# Laser_Driver.net
KiCad netlist of a schematic drawn in EAGLE
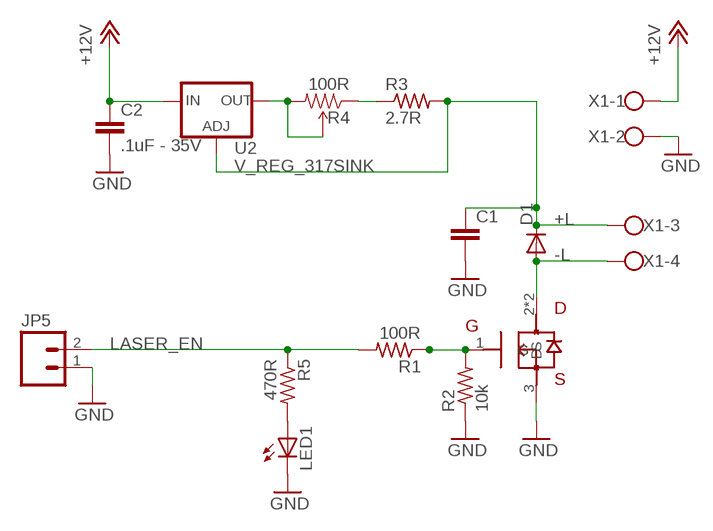
[diagram p0: schematic, sheet 1]

(export (version "E")
  (design (tool "Eeschema 10.0.6"))
  (components
    (comp (ref "C1")
      (value "C-EUC0805")
      (footprint "eagle-import:C0805")
      (libsource (lib "eagle-import") (part "C-EUC0805"))
    )
    (comp (ref "C2")
      (value ".1uF - 35V")
      (footprint "eagle-import:C1206")
      (libsource (lib "eagle-import") (part "C-EUC1206"))
    )
    (comp (ref "D1")
      (value "DIODEPTH")
      (footprint "eagle-import:DIODE-1N4001")
      (libsource (lib "eagle-import") (part "DIODEPTH"))
    )
    (comp (ref "JP5")
      (value "M02PTH")
      (footprint "eagle-import:1X02")
      (libsource (lib "eagle-import") (part "M02PTH"))
    )
    (comp (ref "LED1")
      (value "LEDCHIPLED_0805")
      (footprint "eagle-import:CHIPLED_0805")
      (libsource (lib "eagle-import") (part "LEDCHIPLED_0805"))
    )
    (comp (ref "R1")
      (value "100R")
      (footprint "eagle-import:R0805")
      (libsource (lib "eagle-import") (part "R-US_R0805"))
    )
    (comp (ref "R2")
      (value "10k")
      (footprint "eagle-import:R0805")
      (libsource (lib "eagle-import") (part "R-US_R0805"))
    )
    (comp (ref "R3")
      (value "2.7R")
      (footprint "eagle-import:0411_12")
      (libsource (lib "eagle-import") (part "R-US_0411/12"))
    )
    (comp (ref "R4")
      (value "100R")
      (footprint "eagle-import:3362U-2")
      (libsource (lib "eagle-import") (part "TRIMPOT"))
    )
    (comp (ref "R5")
      (value "470R")
      (footprint "eagle-import:R0805")
      (libsource (lib "eagle-import") (part "R-US_R0805"))
    )
    (comp (ref "U$2")
      (value "MOSFET")
      (footprint "eagle-import:SOT223")
      (libsource (lib "eagle-import") (part "MOSFET"))
    )
    (comp (ref "U2")
      (value "V_REG_317SINK")
      (footprint "eagle-import:TO220-ADJ")
      (libsource (lib "eagle-import") (part "V_REG_317SINK"))
    )
    (comp (ref "X1")
      (value "W237-4")
      (footprint "eagle-import:W237-4")
      (libsource (lib "eagle-import") (part "W237-4"))
    )
  )
  (nets
    (net (code "1") (name "+12V") (class "Default")
      (node (ref "C2") (pin "1") (pinfunction "1_1") (pintype "passive"))
      (node (ref "U2") (pin "IN") (pinfunction "IN_IN") (pintype "input"))
      (node (ref "X1") (pin "1") (pinfunction "KL_1") (pintype "passive"))
    )
    (net (code "2") (name "/+L") (class "Default")
      (node (ref "C1") (pin "1") (pinfunction "1_1") (pintype "passive"))
      (node (ref "D1") (pin "C") (pinfunction "C_C") (pintype "passive"))
      (node (ref "R3") (pin "2") (pinfunction "2_2") (pintype "passive"))
      (node (ref "U2") (pin "ADJ") (pinfunction "ADJ_ADJ") (pintype "input"))
      (node (ref "X1") (pin "3") (pinfunction "KL_3") (pintype "passive"))
    )
    (net (code "3") (name "/-L") (class "Default")
      (node (ref "D1") (pin "A") (pinfunction "A_A") (pintype "passive"))
      (node (ref "U$2") (pin "2") (pinfunction "D_2") (pintype "bidirectional"))
      (node (ref "U$2") (pin "4") (pinfunction "D_4") (pintype "bidirectional"))
      (node (ref "X1") (pin "4") (pinfunction "KL_4") (pintype "passive"))
    )
    (net (code "4") (name "/LASER_EN") (class "Default")
      (node (ref "JP5") (pin "2") (pinfunction "2_2") (pintype "passive"))
      (node (ref "R1") (pin "2") (pinfunction "2_2") (pintype "passive"))
      (node (ref "R5") (pin "1") (pinfunction "1_1") (pintype "passive"))
    )
    (net (code "5") (name "GND") (class "Default")
      (node (ref "C1") (pin "2") (pinfunction "2_2") (pintype "passive"))
      (node (ref "C2") (pin "2") (pinfunction "2_2") (pintype "passive"))
      (node (ref "JP5") (pin "1") (pinfunction "1_1") (pintype "passive"))
      (node (ref "LED1") (pin "C") (pinfunction "C_C") (pintype "passive"))
      (node (ref "R2") (pin "1") (pinfunction "1_1") (pintype "passive"))
      (node (ref "U$2") (pin "3") (pinfunction "S_3") (pintype "bidirectional"))
      (node (ref "X1") (pin "2") (pinfunction "KL_2") (pintype "passive"))
    )
    (net (code "6") (name "Net-(LED1-PadA)") (class "Default")
      (node (ref "LED1") (pin "A") (pinfunction "A_A") (pintype "passive"))
      (node (ref "R5") (pin "2") (pinfunction "2_2") (pintype "passive"))
    )
    (net (code "7") (name "Net-(R4-CCW)") (class "Default")
      (node (ref "R3") (pin "1") (pinfunction "1_1") (pintype "passive"))
      (node (ref "R4") (pin "1") (pinfunction "CCW_1") (pintype "passive"))
    )
    (net (code "8") (name "Net-(R4-CW)") (class "Default")
      (node (ref "R4") (pin "2") (pinfunction "WIPER_2") (pintype "passive"))
      (node (ref "R4") (pin "3") (pinfunction "CW_3") (pintype "passive"))
      (node (ref "U2") (pin "OUT") (pinfunction "OUT_OUT") (pintype "output"))
    )
    (net (code "9") (name "Net-(U$2-G)") (class "Default")
      (node (ref "R1") (pin "1") (pinfunction "1_1") (pintype "passive"))
      (node (ref "R2") (pin "2") (pinfunction "2_2") (pintype "passive"))
      (node (ref "U$2") (pin "1") (pinfunction "G_1") (pintype "bidirectional"))
    )
  )
)
